# untitled.net
KiCad netlist of a schematic drawn in EAGLE
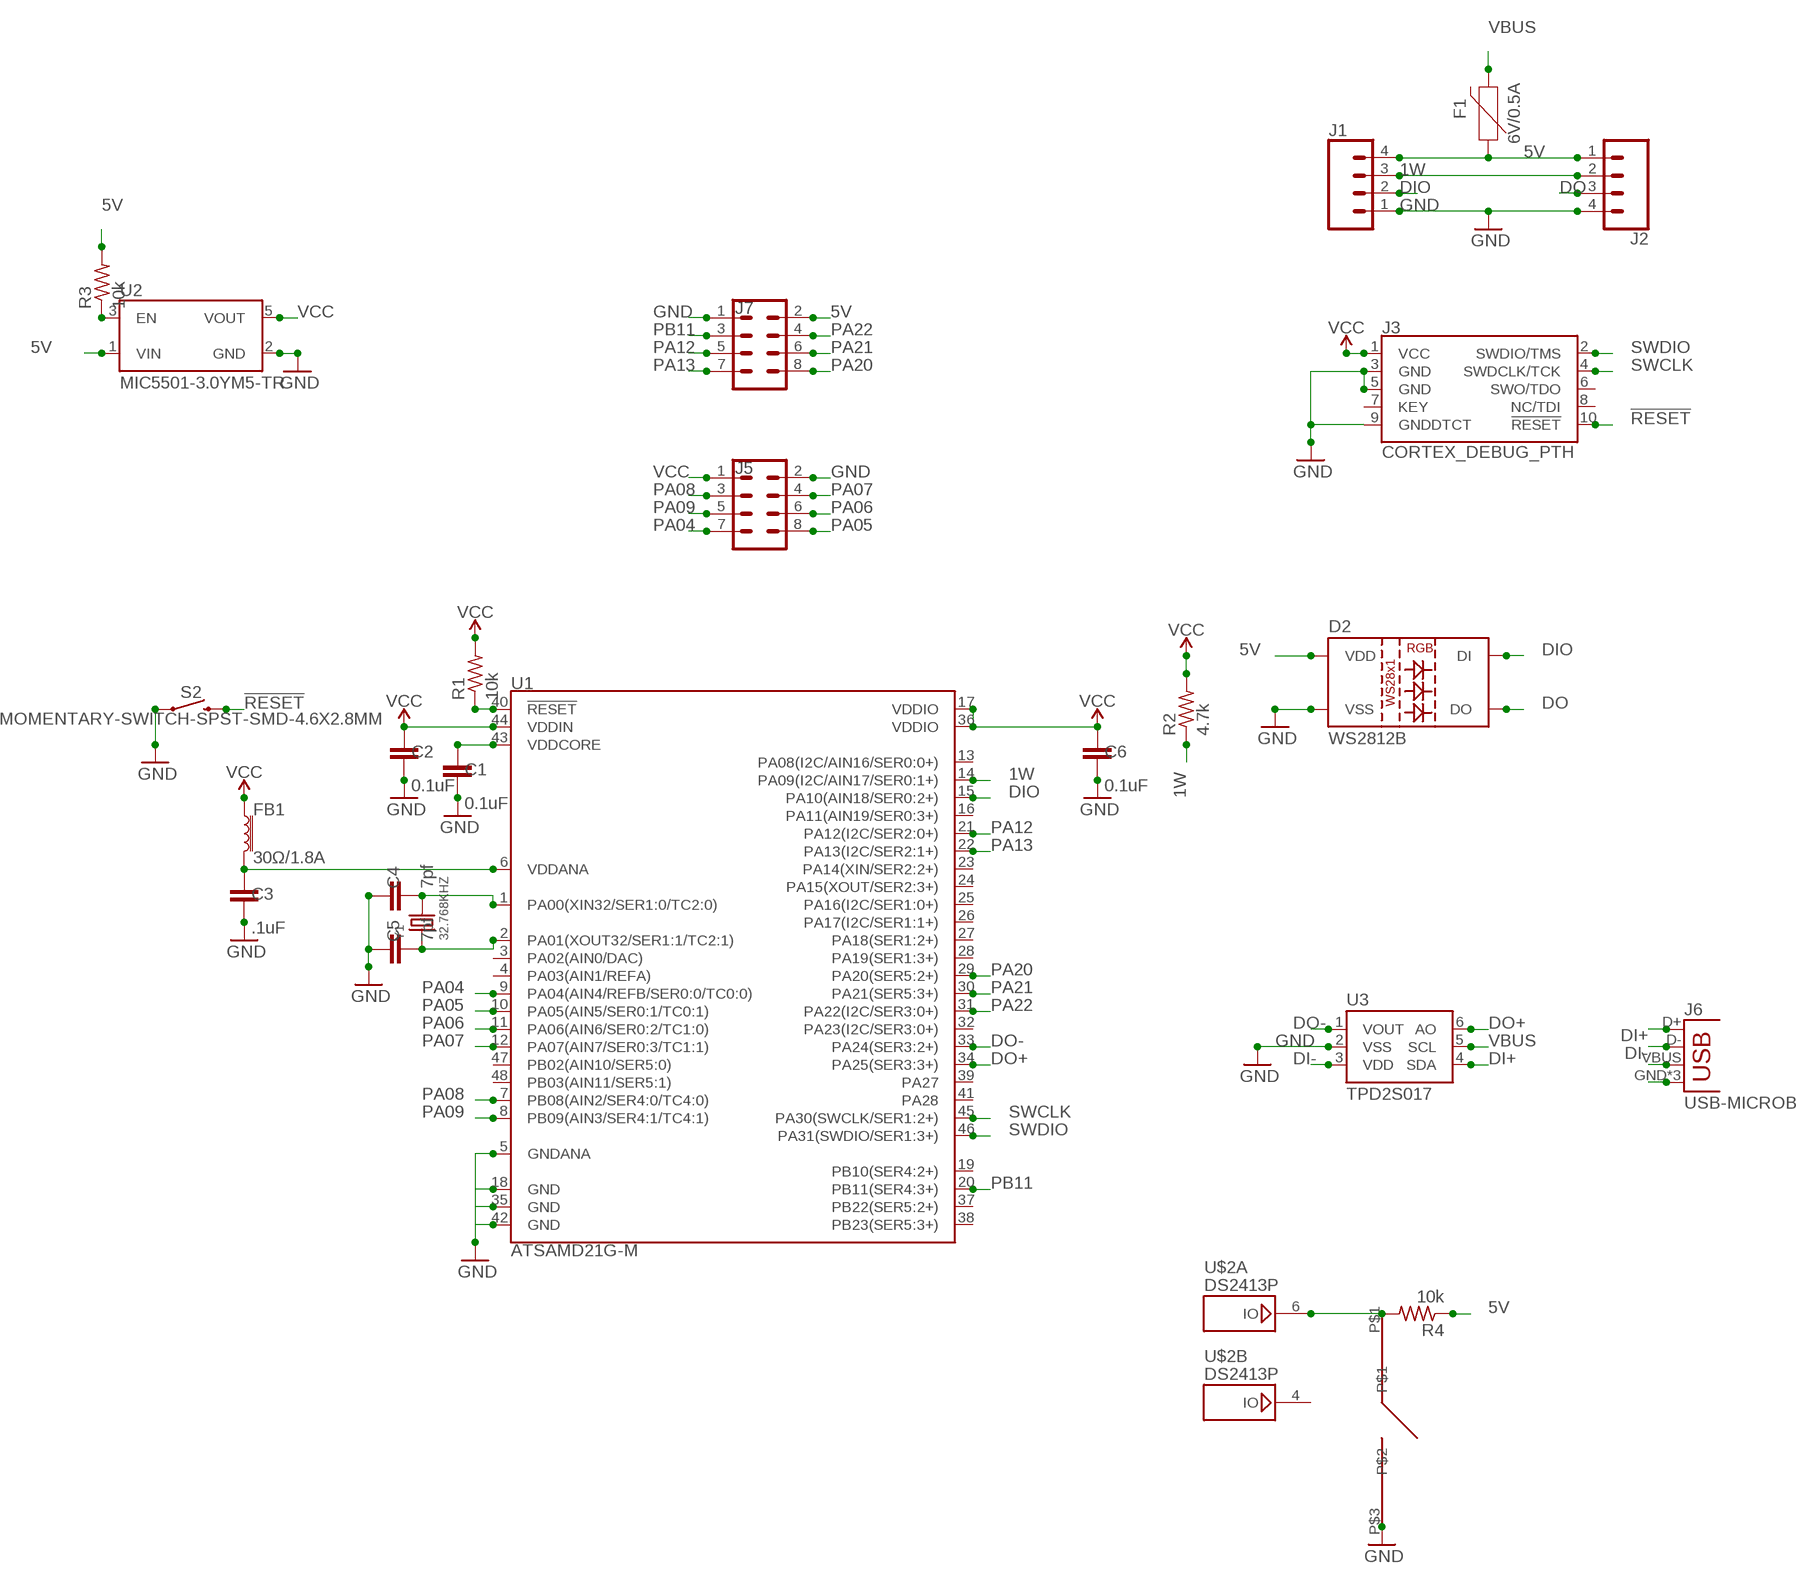
[diagram p0: schematic, sheet 1]

(export (version "E")
  (design (tool "Eeschema 10.0.6"))
  (components
    (comp (ref "C1")
      (value "0.1uF")
      (footprint "eagle-import:0402")
      (libsource (lib "eagle-import") (part "0.1UF-0402-16V-10%"))
    )
    (comp (ref "C2")
      (value "0.1uF")
      (footprint "eagle-import:0402")
      (libsource (lib "eagle-import") (part "0.1UF-0402-16V-10%"))
    )
    (comp (ref "C3")
      (value ".1uF")
      (footprint "eagle-import:0402")
      (libsource (lib "eagle-import") (part "0.1UF-0402-16V-10%"))
    )
    (comp (ref "C4")
      (value "7pf")
      (footprint "eagle-import:0402")
      (libsource (lib "eagle-import") (part "0.1UF-0402-16V-10%"))
    )
    (comp (ref "C5")
      (value "7pf")
      (footprint "eagle-import:0402")
      (libsource (lib "eagle-import") (part "0.1UF-0402-16V-10%"))
    )
    (comp (ref "C6")
      (value "0.1uF")
      (footprint "eagle-import:0402")
      (libsource (lib "eagle-import") (part "0.1UF-0402-16V-10%"))
    )
    (comp (ref "D2")
      (value "WS2812B")
      (footprint "eagle-import:WS2812B")
      (libsource (lib "eagle-import") (part "WS2812B"))
    )
    (comp (ref "F1")
      (value "6V/0.5A")
      (footprint "eagle-import:1206")
      (libsource (lib "eagle-import") (part "PPTC_HALF-AMP"))
    )
    (comp (ref "FB1")
      (value "30Ω/1.8A")
      (footprint "eagle-import:0603")
      (libsource (lib "eagle-import") (part "FERRITE_BEAD-0603"))
    )
    (comp (ref "J1")
      (value "CONN_04SMD2")
      (footprint "eagle-import:1X04_1MM_RA")
      (libsource (lib "eagle-import") (part "CONN_04SMD2"))
    )
    (comp (ref "J2")
      (value "CONN_04SMD2")
      (footprint "eagle-import:1X04_1MM_RA")
      (libsource (lib "eagle-import") (part "CONN_04SMD2"))
    )
    (comp (ref "J3")
      (value "CORTEX_DEBUG_PTH")
      (footprint "eagle-import:2X5-PTH-1.27MM")
      (libsource (lib "eagle-import") (part "CORTEX_DEBUG_PTH"))
    )
    (comp (ref "J5")
      (value "CONN_04X2")
      (footprint "eagle-import:2X4")
      (libsource (lib "eagle-import") (part "CONN_04X2"))
    )
    (comp (ref "J6")
      (value "USB-MICROB")
      (footprint "eagle-import:USB-MICROB")
      (libsource (lib "eagle-import") (part "USB-MICROB"))
    )
    (comp (ref "J7")
      (value "CONN_04X2")
      (footprint "eagle-import:2X4")
      (libsource (lib "eagle-import") (part "CONN_04X2"))
    )
    (comp (ref "R1")
      (value "10k")
      (footprint "eagle-import:R0402")
      (libsource (lib "eagle-import") (part "R-US_R0402"))
    )
    (comp (ref "R2")
      (value "4.7k")
      (footprint "eagle-import:R0402")
      (libsource (lib "eagle-import") (part "R-US_R0402"))
    )
    (comp (ref "R3")
      (value "10k")
      (footprint "eagle-import:R0402")
      (libsource (lib "eagle-import") (part "R-US_R0402"))
    )
    (comp (ref "R4")
      (value "10k")
      (footprint "eagle-import:R0402")
      (libsource (lib "eagle-import") (part "R-US_R0402"))
    )
    (comp (ref "S2")
      (value "MOMENTARY-SWITCH-SPST-SMD-4.6X2.8MM")
      (footprint "eagle-import:TACTILE_SWITCH_SMD_4.6X2.8MM")
      (libsource (lib "eagle-import") (part "MOMENTARY-SWITCH-SPST-SMD-4.6X2.8MM"))
    )
    (comp (ref "U$1")
      (value "NOVELKEY")
      (footprint "eagle-import:NOVELKEY")
      (libsource (lib "eagle-import") (part "NOVELKEY"))
    )
    (comp (ref "U$2")
      (value "DS2413P")
      (footprint "eagle-import:TSOC6")
      (libsource (lib "eagle-import") (part "DS2413P"))
    )
    (comp (ref "U1")
      (value "ATSAMD21G-M")
      (footprint "eagle-import:QFN-48")
      (libsource (lib "eagle-import") (part "ATSAMD21G-M"))
    )
    (comp (ref "U2")
      (value "MIC5501-3.0YM5-TR")
      (footprint "eagle-import:SOT95P280X145-5N")
      (fields (field (name "MF") "Microchip"))
      (libsource (lib "eagle-import") (part "MIC5501-3.0YM5-TR"))
    )
    (comp (ref "U3")
      (value "TPD2S017")
      (footprint "eagle-import:SOT23-6")
      (libsource (lib "eagle-import") (part "MCP4725SOT-23"))
    )
    (comp (ref "Y1")
      (value "32.768KHZ")
      (footprint "eagle-import:X2-SMD-3.2X1.5X0.55MM")
      (fields (field (name "MPN") "FC-135"))
      (libsource (lib "eagle-import") (part "SMD-CRYSTAL-ABS07-32.768KHZ-7PF-20PPM-70K(2P-3.2X1.5MM)"))
    )
  )
  (nets
    (net (code "1") (name "/1W") (class "Default")
      (node (ref "J1") (pin "3") (pinfunction "3_3") (pintype "passive"))
      (node (ref "J2") (pin "2") (pinfunction "2_2") (pintype "passive"))
      (node (ref "R2") (pin "1") (pinfunction "1_1") (pintype "passive"))
      (node (ref "U1") (pin "14") (pinfunction "PA09(I2C/AIN17/SER0:1+)_14") (pintype "bidirectional"))
    )
    (net (code "2") (name "/5V") (class "Default")
      (node (ref "D2") (pin "1") (pinfunction "VDD_1") (pintype "bidirectional"))
      (node (ref "F1") (pin "1") (pinfunction "1_1") (pintype "bidirectional"))
      (node (ref "J1") (pin "4") (pinfunction "4_4") (pintype "passive"))
      (node (ref "J2") (pin "1") (pinfunction "1_1") (pintype "passive"))
      (node (ref "J7") (pin "2") (pinfunction "2_2") (pintype "passive"))
      (node (ref "R3") (pin "2") (pinfunction "2_2") (pintype "passive"))
      (node (ref "R4") (pin "1") (pinfunction "1_1") (pintype "passive"))
      (node (ref "U2") (pin "1") (pinfunction "VIN_1") (pintype "input"))
    )
    (net (code "3") (name "/DI+") (class "Default")
      (node (ref "J6") (pin "D+") (pinfunction "D+_D+") (pintype "bidirectional"))
      (node (ref "U3") (pin "4") (pinfunction "SDA_4") (pintype "bidirectional"))
    )
    (net (code "4") (name "/DI-") (class "Default")
      (node (ref "J6") (pin "D-") (pinfunction "D-_D-") (pintype "bidirectional"))
      (node (ref "U3") (pin "3") (pinfunction "VDD_3") (pintype "bidirectional"))
    )
    (net (code "5") (name "/DIO") (class "Default")
      (node (ref "D2") (pin "4") (pinfunction "DI_4") (pintype "bidirectional"))
      (node (ref "J1") (pin "2") (pinfunction "2_2") (pintype "passive"))
      (node (ref "U1") (pin "15") (pinfunction "PA10(AIN18/SER0:2+)_15") (pintype "bidirectional"))
    )
    (net (code "6") (name "/DO") (class "Default")
      (node (ref "D2") (pin "2") (pinfunction "DO_2") (pintype "bidirectional"))
      (node (ref "J2") (pin "3") (pinfunction "3_3") (pintype "passive"))
    )
    (net (code "7") (name "/DO+") (class "Default")
      (node (ref "U1") (pin "34") (pinfunction "PA25(SER3:3+)_34") (pintype "bidirectional"))
      (node (ref "U3") (pin "6") (pinfunction "AO_6") (pintype "bidirectional"))
    )
    (net (code "8") (name "/DO-") (class "Default")
      (node (ref "U1") (pin "33") (pinfunction "PA24(SER3:2+)_33") (pintype "bidirectional"))
      (node (ref "U3") (pin "1") (pinfunction "VOUT_1") (pintype "bidirectional"))
    )
    (net (code "9") (name "/PA04") (class "Default")
      (node (ref "J5") (pin "7") (pinfunction "7_7") (pintype "passive"))
      (node (ref "U1") (pin "9") (pinfunction "PA04(AIN4/REFB/SER0:0/TC0:0)_9") (pintype "bidirectional"))
    )
    (net (code "10") (name "/PA05") (class "Default")
      (node (ref "J5") (pin "8") (pinfunction "8_8") (pintype "passive"))
      (node (ref "U1") (pin "10") (pinfunction "PA05(AIN5/SER0:1/TC0:1)_10") (pintype "bidirectional"))
    )
    (net (code "11") (name "/PA06") (class "Default")
      (node (ref "J5") (pin "6") (pinfunction "6_6") (pintype "passive"))
      (node (ref "U1") (pin "11") (pinfunction "PA06(AIN6/SER0:2/TC1:0)_11") (pintype "bidirectional"))
    )
    (net (code "12") (name "/PA07") (class "Default")
      (node (ref "J5") (pin "4") (pinfunction "4_4") (pintype "passive"))
      (node (ref "U1") (pin "12") (pinfunction "PA07(AIN7/SER0:3/TC1:1)_12") (pintype "bidirectional"))
    )
    (net (code "13") (name "/PA08") (class "Default")
      (node (ref "J5") (pin "3") (pinfunction "3_3") (pintype "passive"))
      (node (ref "U1") (pin "7") (pinfunction "PB08(AIN2/SER4:0/TC4:0)_7") (pintype "bidirectional"))
    )
    (net (code "14") (name "/PA09") (class "Default")
      (node (ref "J5") (pin "5") (pinfunction "5_5") (pintype "passive"))
      (node (ref "U1") (pin "8") (pinfunction "PB09(AIN3/SER4:1/TC4:1)_8") (pintype "bidirectional"))
    )
    (net (code "15") (name "/PA12") (class "Default")
      (node (ref "J7") (pin "5") (pinfunction "5_5") (pintype "passive"))
      (node (ref "U1") (pin "21") (pinfunction "PA12(I2C/SER2:0+)_21") (pintype "bidirectional"))
    )
    (net (code "16") (name "/PA13") (class "Default")
      (node (ref "J7") (pin "7") (pinfunction "7_7") (pintype "passive"))
      (node (ref "U1") (pin "22") (pinfunction "PA13(I2C/SER2:1+)_22") (pintype "bidirectional"))
    )
    (net (code "17") (name "/PA20") (class "Default")
      (node (ref "J7") (pin "8") (pinfunction "8_8") (pintype "passive"))
      (node (ref "U1") (pin "29") (pinfunction "PA20(SER5:2+)_29") (pintype "bidirectional"))
    )
    (net (code "18") (name "/PA21") (class "Default")
      (node (ref "J7") (pin "6") (pinfunction "6_6") (pintype "passive"))
      (node (ref "U1") (pin "30") (pinfunction "PA21(SER5:3+)_30") (pintype "bidirectional"))
    )
    (net (code "19") (name "/PA22") (class "Default")
      (node (ref "J7") (pin "4") (pinfunction "4_4") (pintype "passive"))
      (node (ref "U1") (pin "31") (pinfunction "PA22(I2C/SER3:0+)_31") (pintype "bidirectional"))
    )
    (net (code "20") (name "/PB11") (class "Default")
      (node (ref "J7") (pin "3") (pinfunction "3_3") (pintype "passive"))
      (node (ref "U1") (pin "20") (pinfunction "PB11(SER4:3+)_20") (pintype "bidirectional"))
    )
    (net (code "21") (name "/SWCLK") (class "Default")
      (node (ref "J3") (pin "4") (pinfunction "SWDCLK/TCK_4") (pintype "bidirectional"))
      (node (ref "U1") (pin "45") (pinfunction "PA30(SWCLK/SER1:2+)_45") (pintype "bidirectional"))
    )
    (net (code "22") (name "/SWDIO") (class "Default")
      (node (ref "J3") (pin "2") (pinfunction "SWDIO/TMS_2") (pintype "bidirectional"))
      (node (ref "U1") (pin "46") (pinfunction "PA31(SWDIO/SER1:3+)_46") (pintype "bidirectional"))
    )
    (net (code "23") (name "/VBUS") (class "Default")
      (node (ref "F1") (pin "2") (pinfunction "2_2") (pintype "bidirectional"))
      (node (ref "J6") (pin "VBUS") (pinfunction "VBUS_VBUS") (pintype "bidirectional"))
      (node (ref "U3") (pin "5") (pinfunction "SCL_5") (pintype "bidirectional"))
    )
    (net (code "24") (name "/~{RESET}") (class "Default")
      (node (ref "J3") (pin "10") (pinfunction "~{RESET}_10") (pintype "bidirectional"))
      (node (ref "R1") (pin "1") (pinfunction "1_1") (pintype "passive"))
      (node (ref "S2") (pin "3") (pinfunction "2_3") (pintype "passive"))
      (node (ref "S2") (pin "4") (pinfunction "2_4") (pintype "passive"))
      (node (ref "U1") (pin "40") (pinfunction "~{RESET}_40") (pintype "bidirectional"))
    )
    (net (code "25") (name "GND") (class "Default")
      (node (ref "C1") (pin "2") (pinfunction "2_2") (pintype "passive"))
      (node (ref "C2") (pin "2") (pinfunction "2_2") (pintype "passive"))
      (node (ref "C3") (pin "2") (pinfunction "2_2") (pintype "passive"))
      (node (ref "C4") (pin "1") (pinfunction "1_1") (pintype "passive"))
      (node (ref "C5") (pin "1") (pinfunction "1_1") (pintype "passive"))
      (node (ref "C6") (pin "2") (pinfunction "2_2") (pintype "passive"))
      (node (ref "D2") (pin "3") (pinfunction "VSS_3") (pintype "bidirectional"))
      (node (ref "J1") (pin "1") (pinfunction "1_1") (pintype "passive"))
      (node (ref "J2") (pin "4") (pinfunction "4_4") (pintype "passive"))
      (node (ref "J3") (pin "3") (pinfunction "GND_3") (pintype "bidirectional"))
      (node (ref "J3") (pin "5") (pinfunction "GND_5") (pintype "bidirectional"))
      (node (ref "J3") (pin "9") (pinfunction "GNDDTCT_9") (pintype "bidirectional"))
      (node (ref "J5") (pin "2") (pinfunction "2_2") (pintype "passive"))
      (node (ref "J6") (pin "GND") (pinfunction "GND_GND") (pintype "bidirectional"))
      (node (ref "J6") (pin "MT1") (pinfunction "GND_MT1") (pintype "bidirectional"))
      (node (ref "J6") (pin "MT2") (pinfunction "GND_MT2") (pintype "bidirectional"))
      (node (ref "J7") (pin "1") (pinfunction "1_1") (pintype "passive"))
      (node (ref "S2") (pin "1") (pinfunction "1_1") (pintype "passive"))
      (node (ref "S2") (pin "2") (pinfunction "1_2") (pintype "passive"))
      (node (ref "U$1") (pin "P$3") (pinfunction "P$2_P$3") (pintype "bidirectional"))
      (node (ref "U1") (pin "18") (pinfunction "GND_18") (pintype "bidirectional"))
      (node (ref "U1") (pin "35") (pinfunction "GND_35") (pintype "bidirectional"))
      (node (ref "U1") (pin "42") (pinfunction "GND_42") (pintype "bidirectional"))
      (node (ref "U1") (pin "5") (pinfunction "GNDANA_5") (pintype "bidirectional"))
      (node (ref "U2") (pin "2") (pinfunction "GND_2") (pintype "power_in"))
      (node (ref "U3") (pin "2") (pinfunction "VSS_2") (pintype "bidirectional"))
    )
    (net (code "26") (name "Net-(U$2A-IO)") (class "Default")
      (node (ref "R4") (pin "2") (pinfunction "2_2") (pintype "passive"))
      (node (ref "U$1") (pin "P$1") (pinfunction "P$1_P$1") (pintype "bidirectional"))
      (node (ref "U$2") (pin "6") (pinfunction "IO_6") (pintype "open_collector"))
    )
    (net (code "27") (name "Net-(U1-PA00(XIN32{slash}SER1:0{slash}TC2:0))") (class "Default")
      (node (ref "C4") (pin "2") (pinfunction "2_2") (pintype "passive"))
      (node (ref "U1") (pin "1") (pinfunction "PA00(XIN32/SER1:0/TC2:0)_1") (pintype "bidirectional"))
      (node (ref "Y1") (pin "2") (pinfunction "2_2") (pintype "passive"))
    )
    (net (code "28") (name "Net-(U1-PA01(XOUT32{slash}SER1:1{slash}TC2:1))") (class "Default")
      (node (ref "C5") (pin "2") (pinfunction "2_2") (pintype "passive"))
      (node (ref "U1") (pin "2") (pinfunction "PA01(XOUT32/SER1:1/TC2:1)_2") (pintype "bidirectional"))
      (node (ref "Y1") (pin "1") (pinfunction "1_1") (pintype "passive"))
    )
    (net (code "29") (name "Net-(U1-VDDANA)") (class "Default")
      (node (ref "C3") (pin "1") (pinfunction "1_1") (pintype "passive"))
      (node (ref "FB1") (pin "2") (pinfunction "2_2") (pintype "passive"))
      (node (ref "U1") (pin "6") (pinfunction "VDDANA_6") (pintype "bidirectional"))
    )
    (net (code "30") (name "Net-(U1-VDDCORE)") (class "Default")
      (node (ref "C1") (pin "1") (pinfunction "1_1") (pintype "passive"))
      (node (ref "U1") (pin "43") (pinfunction "VDDCORE_43") (pintype "bidirectional"))
    )
    (net (code "31") (name "Net-(U2-EN)") (class "Default")
      (node (ref "R3") (pin "1") (pinfunction "1_1") (pintype "passive"))
      (node (ref "U2") (pin "3") (pinfunction "EN_3") (pintype "input"))
    )
    (net (code "32") (name "VCC") (class "Default")
      (node (ref "C2") (pin "1") (pinfunction "1_1") (pintype "passive"))
      (node (ref "C6") (pin "1") (pinfunction "1_1") (pintype "passive"))
      (node (ref "FB1") (pin "1") (pinfunction "1_1") (pintype "passive"))
      (node (ref "J3") (pin "1") (pinfunction "VCC_1") (pintype "bidirectional"))
      (node (ref "J5") (pin "1") (pinfunction "1_1") (pintype "passive"))
      (node (ref "R1") (pin "2") (pinfunction "2_2") (pintype "passive"))
      (node (ref "R2") (pin "2") (pinfunction "2_2") (pintype "passive"))
      (node (ref "U1") (pin "17") (pinfunction "VDDIO_17") (pintype "bidirectional"))
      (node (ref "U1") (pin "36") (pinfunction "VDDIO_36") (pintype "bidirectional"))
      (node (ref "U1") (pin "44") (pinfunction "VDDIN_44") (pintype "bidirectional"))
      (node (ref "U2") (pin "5") (pinfunction "VOUT_5") (pintype "output"))
    )
    (net (code "33") (name "unconnected-(J3-KEY-Pad7)") (class "Default")
      (node (ref "J3") (pin "7") (pinfunction "KEY_7") (pintype "bidirectional"))
    )
    (net (code "34") (name "unconnected-(J3-NC{slash}TDI-Pad8)") (class "Default")
      (node (ref "J3") (pin "8") (pinfunction "NC/TDI_8") (pintype "bidirectional"))
    )
    (net (code "35") (name "unconnected-(J3-SWO{slash}TDO-Pad6)") (class "Default")
      (node (ref "J3") (pin "6") (pinfunction "SWO/TDO_6") (pintype "bidirectional"))
    )
    (net (code "36") (name "unconnected-(U$2B-IO-Pad4)") (class "Default")
      (node (ref "U$2") (pin "4") (pinfunction "IO_4") (pintype "open_collector"))
    )
    (net (code "37") (name "unconnected-(U1-PA02(AIN0{slash}DAC)-Pad3)") (class "Default")
      (node (ref "U1") (pin "3") (pinfunction "PA02(AIN0/DAC)_3") (pintype "bidirectional"))
    )
    (net (code "38") (name "unconnected-(U1-PA03(AIN1{slash}REFA)-Pad4)") (class "Default")
      (node (ref "U1") (pin "4") (pinfunction "PA03(AIN1/REFA)_4") (pintype "bidirectional"))
    )
    (net (code "39") (name "unconnected-(U1-PA08(I2C{slash}AIN16{slash}SER0:0+)-Pad13)") (class "Default")
      (node (ref "U1") (pin "13") (pinfunction "PA08(I2C/AIN16/SER0:0+)_13") (pintype "bidirectional"))
    )
    (net (code "40") (name "unconnected-(U1-PA11(AIN19{slash}SER0:3+)-Pad16)") (class "Default")
      (node (ref "U1") (pin "16") (pinfunction "PA11(AIN19/SER0:3+)_16") (pintype "bidirectional"))
    )
    (net (code "41") (name "unconnected-(U1-PA14(XIN{slash}SER2:2+)-Pad23)") (class "Default")
      (node (ref "U1") (pin "23") (pinfunction "PA14(XIN/SER2:2+)_23") (pintype "bidirectional"))
    )
    (net (code "42") (name "unconnected-(U1-PA15(XOUT{slash}SER2:3+)-Pad24)") (class "Default")
      (node (ref "U1") (pin "24") (pinfunction "PA15(XOUT/SER2:3+)_24") (pintype "bidirectional"))
    )
    (net (code "43") (name "unconnected-(U1-PA16(I2C{slash}SER1:0+)-Pad25)") (class "Default")
      (node (ref "U1") (pin "25") (pinfunction "PA16(I2C/SER1:0+)_25") (pintype "bidirectional"))
    )
    (net (code "44") (name "unconnected-(U1-PA17(I2C{slash}SER1:1+)-Pad26)") (class "Default")
      (node (ref "U1") (pin "26") (pinfunction "PA17(I2C/SER1:1+)_26") (pintype "bidirectional"))
    )
    (net (code "45") (name "unconnected-(U1-PA18(SER1:2+)-Pad27)") (class "Default")
      (node (ref "U1") (pin "27") (pinfunction "PA18(SER1:2+)_27") (pintype "bidirectional"))
    )
    (net (code "46") (name "unconnected-(U1-PA19(SER1:3+)-Pad28)") (class "Default")
      (node (ref "U1") (pin "28") (pinfunction "PA19(SER1:3+)_28") (pintype "bidirectional"))
    )
    (net (code "47") (name "unconnected-(U1-PA23(I2C{slash}SER3:0+)-Pad32)") (class "Default")
      (node (ref "U1") (pin "32") (pinfunction "PA23(I2C/SER3:0+)_32") (pintype "bidirectional"))
    )
    (net (code "48") (name "unconnected-(U1-PA27-Pad39)") (class "Default")
      (node (ref "U1") (pin "39") (pinfunction "PA27_39") (pintype "bidirectional"))
    )
    (net (code "49") (name "unconnected-(U1-PA28-Pad41)") (class "Default")
      (node (ref "U1") (pin "41") (pinfunction "PA28_41") (pintype "bidirectional"))
    )
    (net (code "50") (name "unconnected-(U1-PB02(AIN10{slash}SER5:0)-Pad47)") (class "Default")
      (node (ref "U1") (pin "47") (pinfunction "PB02(AIN10/SER5:0)_47") (pintype "bidirectional"))
    )
    (net (code "51") (name "unconnected-(U1-PB03(AIN11{slash}SER5:1)-Pad48)") (class "Default")
      (node (ref "U1") (pin "48") (pinfunction "PB03(AIN11/SER5:1)_48") (pintype "bidirectional"))
    )
    (net (code "52") (name "unconnected-(U1-PB10(SER4:2+)-Pad19)") (class "Default")
      (node (ref "U1") (pin "19") (pinfunction "PB10(SER4:2+)_19") (pintype "bidirectional"))
    )
    (net (code "53") (name "unconnected-(U1-PB22(SER5:2+)-Pad37)") (class "Default")
      (node (ref "U1") (pin "37") (pinfunction "PB22(SER5:2+)_37") (pintype "bidirectional"))
    )
    (net (code "54") (name "unconnected-(U1-PB23(SER5:3+)-Pad38)") (class "Default")
      (node (ref "U1") (pin "38") (pinfunction "PB23(SER5:3+)_38") (pintype "bidirectional"))
    )
  )
)
